# SingleMatrix.net
KiCad netlist of a schematic drawn in Altium Designer
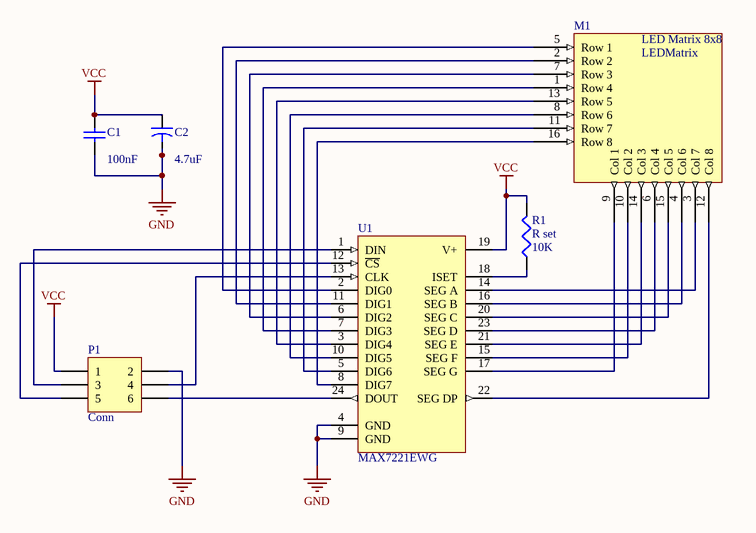
[diagram p0: SingleMatrix.SchDoc]

(export (version "E")
  (design (tool "Eeschema 10.0.6"))
  (components
    (comp (ref "C1")
      (value "100nF")
      (footprint "C1206")
      (description "Capacitor (Semiconductor SIM Model)")
      (fields (field (name "PUBLISHER") "Altium Limited"))
      (libsource (lib "Miscellaneous Devices") (part "Cap Semi"))
    )
    (comp (ref "C2")
      (value "4.7uF")
      (footprint "CAPR5-4X5")
      (description "Capacitor")
      (fields (field (name "PUBLISHER") "Altium Limited"))
      (libsource (lib "Miscellaneous Devices") (part "Cap2"))
    )
    (comp (ref "M1")
      (value "LEDMatrix")
      (footprint "LEDMATRIX")
      (description "LED Matrix 8x8 white")
      (libsource (lib "LEDMatrix") (part "LEDMatrix"))
    )
    (comp (ref "P1")
      (value "Conn")
      (footprint "HDR2X3H")
      (description "Header, 3-Pin, Dual row, Right Angle")
      (fields (field (name "PUBLISHER") "Altium Limited"))
      (libsource (lib "Miscellaneous Connectors") (part "Header 3X2H"))
    )
    (comp (ref "R1")
      (value "R set")
      (footprint "6-0805_N")
      (description "Resistor")
      (fields (field (name "ALTIUM_VALUE") "10K") (field (name "PUBLISHER") "Altium Limited"))
      (libsource (lib "Miscellaneous Devices") (part "Res3"))
    )
    (comp (ref "U1")
      (value "MAX7221EWG")
      (footprint "WSO24_M")
      (description "Serially Interfaced, 8-Digit LED Display Driver")
      (fields (field (name "PUBLISHER") "Altium Limited"))
      (libsource (lib "Maxim Interface Display Driver") (part "MAX7221EWG"))
    )
  )
  (nets
    (net (code "1") (name "GND") (class "Default")
      (node (ref "C1") (pin "1") (pinfunction "1_1") (pintype "passive"))
      (node (ref "C2") (pin "2") (pinfunction "2_2") (pintype "passive"))
      (node (ref "P1") (pin "2") (pinfunction "2_2") (pintype "passive"))
      (node (ref "U1") (pin "4") (pinfunction "GND_4") (pintype "power_in"))
      (node (ref "U1") (pin "9") (pinfunction "GND_9") (pintype "power_in"))
    )
    (net (code "2") (name "Net-(M1-Col_1)") (class "Default")
      (node (ref "M1") (pin "9") (pinfunction "Col_1_9") (pintype "output"))
      (node (ref "U1") (pin "17") (pinfunction "SEG_G_17") (pintype "tri_state"))
    )
    (net (code "3") (name "Net-(M1-Col_2)") (class "Default")
      (node (ref "M1") (pin "10") (pinfunction "Col_2_10") (pintype "output"))
      (node (ref "U1") (pin "15") (pinfunction "SEG_F_15") (pintype "tri_state"))
    )
    (net (code "4") (name "Net-(M1-Col_3)") (class "Default")
      (node (ref "M1") (pin "14") (pinfunction "Col_3_14") (pintype "output"))
      (node (ref "U1") (pin "21") (pinfunction "SEG_E_21") (pintype "tri_state"))
    )
    (net (code "5") (name "Net-(M1-Col_4)") (class "Default")
      (node (ref "M1") (pin "6") (pinfunction "Col_4_6") (pintype "output"))
      (node (ref "U1") (pin "23") (pinfunction "SEG_D_23") (pintype "tri_state"))
    )
    (net (code "6") (name "Net-(M1-Col_5)") (class "Default")
      (node (ref "M1") (pin "15") (pinfunction "Col_5_15") (pintype "output"))
      (node (ref "U1") (pin "20") (pinfunction "SEG_C_20") (pintype "tri_state"))
    )
    (net (code "7") (name "Net-(M1-Col_6)") (class "Default")
      (node (ref "M1") (pin "4") (pinfunction "Col_6_4") (pintype "output"))
      (node (ref "U1") (pin "16") (pinfunction "SEG_B_16") (pintype "tri_state"))
    )
    (net (code "8") (name "Net-(M1-Col_7)") (class "Default")
      (node (ref "M1") (pin "3") (pinfunction "Col_7_3") (pintype "output"))
      (node (ref "U1") (pin "14") (pinfunction "SEG_A_14") (pintype "tri_state"))
    )
    (net (code "9") (name "Net-(M1-Col_8)") (class "Default")
      (node (ref "M1") (pin "12") (pinfunction "Col_8_12") (pintype "output"))
      (node (ref "U1") (pin "22") (pinfunction "SEG_DP_22") (pintype "output"))
    )
    (net (code "10") (name "Net-(M1-Row_1)") (class "Default")
      (node (ref "M1") (pin "5") (pinfunction "Row_1_5") (pintype "input"))
      (node (ref "U1") (pin "2") (pinfunction "DIG0_2") (pintype "tri_state"))
    )
    (net (code "11") (name "Net-(M1-Row_2)") (class "Default")
      (node (ref "M1") (pin "2") (pinfunction "Row_2_2") (pintype "input"))
      (node (ref "U1") (pin "11") (pinfunction "DIG1_11") (pintype "tri_state"))
    )
    (net (code "12") (name "Net-(M1-Row_3)") (class "Default")
      (node (ref "M1") (pin "7") (pinfunction "Row_3_7") (pintype "input"))
      (node (ref "U1") (pin "6") (pinfunction "DIG2_6") (pintype "tri_state"))
    )
    (net (code "13") (name "Net-(M1-Row_4)") (class "Default")
      (node (ref "M1") (pin "1") (pinfunction "Row_4_1") (pintype "input"))
      (node (ref "U1") (pin "7") (pinfunction "DIG3_7") (pintype "tri_state"))
    )
    (net (code "14") (name "Net-(M1-Row_5)") (class "Default")
      (node (ref "M1") (pin "13") (pinfunction "Row_5_13") (pintype "input"))
      (node (ref "U1") (pin "3") (pinfunction "DIG4_3") (pintype "tri_state"))
    )
    (net (code "15") (name "Net-(M1-Row_6)") (class "Default")
      (node (ref "M1") (pin "8") (pinfunction "Row_6_8") (pintype "input"))
      (node (ref "U1") (pin "10") (pinfunction "DIG5_10") (pintype "tri_state"))
    )
    (net (code "16") (name "Net-(M1-Row_7)") (class "Default")
      (node (ref "M1") (pin "11") (pinfunction "Row_7_11") (pintype "input"))
      (node (ref "U1") (pin "5") (pinfunction "DIG6_5") (pintype "tri_state"))
    )
    (net (code "17") (name "Net-(M1-Row_8)") (class "Default")
      (node (ref "M1") (pin "16") (pinfunction "Row_8_16") (pintype "input"))
      (node (ref "U1") (pin "8") (pinfunction "DIG7_8") (pintype "tri_state"))
    )
    (net (code "18") (name "Net-(U1-CLK)") (class "Default")
      (node (ref "P1") (pin "4") (pinfunction "4_4") (pintype "passive"))
      (node (ref "U1") (pin "13") (pinfunction "CLK_13") (pintype "input"))
    )
    (net (code "19") (name "Net-(U1-DIN)") (class "Default")
      (node (ref "P1") (pin "3") (pinfunction "3_3") (pintype "passive"))
      (node (ref "U1") (pin "1") (pinfunction "DIN_1") (pintype "input"))
    )
    (net (code "20") (name "Net-(U1-DOUT)") (class "Default")
      (node (ref "P1") (pin "6") (pinfunction "6_6") (pintype "passive"))
      (node (ref "U1") (pin "24") (pinfunction "DOUT_24") (pintype "output"))
    )
    (net (code "21") (name "Net-(U1-ISET)") (class "Default")
      (node (ref "R1") (pin "1") (pinfunction "1_1") (pintype "passive"))
      (node (ref "U1") (pin "18") (pinfunction "ISET_18") (pintype "passive"))
    )
    (net (code "22") (name "Net-(U1-~{CS})") (class "Default")
      (node (ref "P1") (pin "5") (pinfunction "5_5") (pintype "passive"))
      (node (ref "U1") (pin "12") (pinfunction "~{CS}_12") (pintype "input"))
    )
    (net (code "23") (name "VCC") (class "Default")
      (node (ref "C1") (pin "2") (pinfunction "2_2") (pintype "passive"))
      (node (ref "C2") (pin "1") (pinfunction "1_1") (pintype "passive"))
      (node (ref "P1") (pin "1") (pinfunction "1_1") (pintype "passive"))
      (node (ref "R1") (pin "2") (pinfunction "2_2") (pintype "passive"))
      (node (ref "U1") (pin "19") (pinfunction "V+_19") (pintype "power_in"))
    )
  )
)
